# TPS5313.net
KiCad netlist of a schematic drawn in Altium Designer
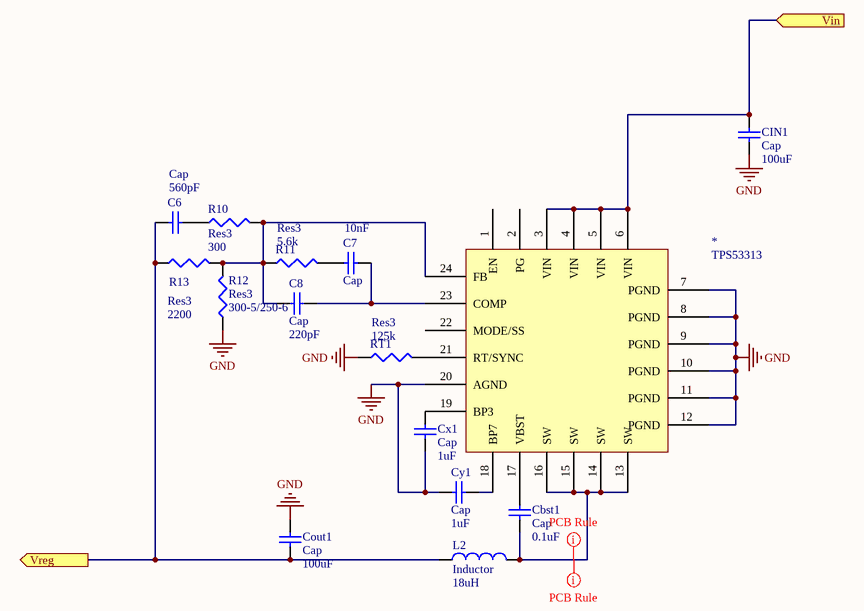
[diagram p0: TPS5313.SchDoc]

(export (version "E")
  (design (tool "Eeschema 10.0.6"))
  (components
    (comp (ref "*")
      (value "TPS53313")
      (footprint "RGE24_2P45X2P45")
      (libsource (lib "InvestiGator") (part "TPS53313"))
    )
    (comp (ref "C6")
      (value "Cap")
      (footprint "C0805")
      (description "Capacitor")
      (fields (field (name "ALTIUM_VALUE") "560pF") (field (name "PUBLISHER") "Altium Limited"))
      (libsource (lib "Miscellaneous Devices") (part "Cap"))
    )
    (comp (ref "C7")
      (value "Cap")
      (footprint "C0805")
      (description "Capacitor")
      (fields (field (name "ALTIUM_VALUE") "10nF") (field (name "PUBLISHER") "Altium Limited"))
      (libsource (lib "Miscellaneous Devices") (part "Cap"))
    )
    (comp (ref "C8")
      (value "Cap")
      (footprint "C0805")
      (description "Capacitor")
      (fields (field (name "ALTIUM_VALUE") "220pF") (field (name "PUBLISHER") "Altium Limited"))
      (libsource (lib "Miscellaneous Devices") (part "Cap"))
    )
    (comp (ref "Cbst1")
      (value "Cap")
      (footprint "C0805")
      (description "Capacitor")
      (fields (field (name "ALTIUM_VALUE") "0.1uF") (field (name "PUBLISHER") "Altium Limited"))
      (libsource (lib "Miscellaneous Devices") (part "Cap"))
    )
    (comp (ref "CIN1")
      (value "Cap")
      (footprint "C0805")
      (description "Capacitor")
      (fields (field (name "ALTIUM_VALUE") "100uF") (field (name "PUBLISHER") "Altium Limited"))
      (libsource (lib "Miscellaneous Devices") (part "Cap"))
    )
    (comp (ref "Cout1")
      (value "Cap")
      (footprint "C0805")
      (description "Capacitor")
      (fields (field (name "ALTIUM_VALUE") "100uF") (field (name "PUBLISHER") "Altium Limited"))
      (libsource (lib "Miscellaneous Devices") (part "Cap"))
    )
    (comp (ref "Cx1")
      (value "Cap")
      (footprint "C0805")
      (description "Capacitor")
      (fields (field (name "ALTIUM_VALUE") "1uF") (field (name "PUBLISHER") "Altium Limited"))
      (libsource (lib "Miscellaneous Devices") (part "Cap"))
    )
    (comp (ref "Cy1")
      (value "Cap")
      (footprint "C0805")
      (description "Capacitor")
      (fields (field (name "ALTIUM_VALUE") "1uF") (field (name "PUBLISHER") "Altium Limited"))
      (libsource (lib "Miscellaneous Devices") (part "Cap"))
    )
    (comp (ref "L2")
      (value "Inductor")
      (footprint "6-0805_L")
      (fields (field (name "ALTIUM_VALUE") "18uH") (field (name "PUBLISHER") "Altium Limited"))
      (libsource (lib "Miscellaneous Devices") (part "Inductor"))
    )
    (comp (ref "R10")
      (value "Res3")
      (footprint "6-0805_M")
      (description "Resistor")
      (fields (field (name "ALTIUM_VALUE") "300") (field (name "PUBLISHER") "Altium Limited"))
      (libsource (lib "Miscellaneous Devices") (part "Res3"))
    )
    (comp (ref "R11")
      (value "Res3")
      (footprint "6-0805_M")
      (description "Resistor")
      (fields (field (name "ALTIUM_VALUE") "5.6k") (field (name "PUBLISHER") "Altium Limited"))
      (libsource (lib "Miscellaneous Devices") (part "Res3"))
    )
    (comp (ref "R12")
      (value "Res3")
      (footprint "6-0805_M")
      (description "Resistor")
      (fields (field (name "ALTIUM_VALUE") "300-5/250-6") (field (name "PUBLISHER") "Altium Limited"))
      (libsource (lib "Miscellaneous Devices") (part "Res3"))
    )
    (comp (ref "R13")
      (value "Res3")
      (footprint "6-0805_M")
      (description "Resistor")
      (fields (field (name "ALTIUM_VALUE") "2200") (field (name "PUBLISHER") "Altium Limited"))
      (libsource (lib "Miscellaneous Devices") (part "Res3"))
    )
    (comp (ref "RT1")
      (value "Res3")
      (footprint "6-0805_M")
      (description "Resistor")
      (fields (field (name "ALTIUM_VALUE") "125k") (field (name "PUBLISHER") "Altium Limited"))
      (libsource (lib "Miscellaneous Devices") (part "Res3"))
    )
  )
  (nets
    (net (code "1") (name "/Vin") (class "Default")
      (node (ref "*") (pin "3") (pinfunction "VIN_3") (pintype "passive"))
      (node (ref "*") (pin "4") (pinfunction "VIN_4") (pintype "passive"))
      (node (ref "*") (pin "5") (pinfunction "VIN_5") (pintype "passive"))
      (node (ref "*") (pin "6") (pinfunction "VIN_6") (pintype "passive"))
      (node (ref "CIN1") (pin "1") (pinfunction "1_1") (pintype "passive"))
    )
    (net (code "2") (name "/Vreg") (class "Default")
      (node (ref "C6") (pin "1") (pinfunction "1_1") (pintype "passive"))
      (node (ref "Cout1") (pin "1") (pinfunction "1_1") (pintype "passive"))
      (node (ref "L2") (pin "1") (pinfunction "1_1") (pintype "passive"))
      (node (ref "R13") (pin "1") (pinfunction "1_1") (pintype "passive"))
    )
    (net (code "3") (name "GND") (class "Default")
      (node (ref "*") (pin "10") (pinfunction "PGND_10") (pintype "passive"))
      (node (ref "*") (pin "11") (pinfunction "PGND_11") (pintype "passive"))
      (node (ref "*") (pin "12") (pinfunction "PGND_12") (pintype "passive"))
      (node (ref "*") (pin "20") (pinfunction "AGND_20") (pintype "power_in"))
      (node (ref "*") (pin "7") (pinfunction "PGND_7") (pintype "passive"))
      (node (ref "*") (pin "8") (pinfunction "PGND_8") (pintype "passive"))
      (node (ref "*") (pin "9") (pinfunction "PGND_9") (pintype "passive"))
      (node (ref "CIN1") (pin "2") (pinfunction "2_2") (pintype "passive"))
      (node (ref "Cout1") (pin "2") (pinfunction "2_2") (pintype "passive"))
      (node (ref "Cx1") (pin "1") (pinfunction "1_1") (pintype "passive"))
      (node (ref "Cy1") (pin "2") (pinfunction "2_2") (pintype "passive"))
      (node (ref "R12") (pin "1") (pinfunction "1_1") (pintype "passive"))
      (node (ref "RT1") (pin "1") (pinfunction "1_1") (pintype "passive"))
    )
    (net (code "4") (name "Net-(*-BP3)") (class "Default")
      (node (ref "*") (pin "19") (pinfunction "BP3_19") (pintype "power_in"))
      (node (ref "Cx1") (pin "2") (pinfunction "2_2") (pintype "passive"))
    )
    (net (code "5") (name "Net-(*-BP7)") (class "Default")
      (node (ref "*") (pin "18") (pinfunction "BP7_18") (pintype "power_in"))
      (node (ref "Cy1") (pin "1") (pinfunction "1_1") (pintype "passive"))
    )
    (net (code "6") (name "Net-(*-COMP)") (class "Default")
      (node (ref "*") (pin "23") (pinfunction "COMP_23") (pintype "passive"))
      (node (ref "C7") (pin "2") (pinfunction "2_2") (pintype "passive"))
      (node (ref "C8") (pin "2") (pinfunction "2_2") (pintype "passive"))
    )
    (net (code "7") (name "Net-(*-FB)") (class "Default")
      (node (ref "*") (pin "24") (pinfunction "FB_24") (pintype "passive"))
      (node (ref "C8") (pin "1") (pinfunction "1_1") (pintype "passive"))
      (node (ref "R10") (pin "2") (pinfunction "2_2") (pintype "passive"))
      (node (ref "R11") (pin "1") (pinfunction "1_1") (pintype "passive"))
      (node (ref "R12") (pin "2") (pinfunction "2_2") (pintype "passive"))
      (node (ref "R13") (pin "2") (pinfunction "2_2") (pintype "passive"))
    )
    (net (code "8") (name "Net-(*-RT{slash}SYNC)") (class "Default")
      (node (ref "*") (pin "21") (pinfunction "RT/SYNC_21") (pintype "passive"))
      (node (ref "RT1") (pin "2") (pinfunction "2_2") (pintype "passive"))
    )
    (net (code "9") (name "Net-(*-SW-Pad13)") (class "Default")
      (node (ref "*") (pin "13") (pinfunction "SW_13") (pintype "passive"))
      (node (ref "*") (pin "14") (pinfunction "SW_14") (pintype "passive"))
      (node (ref "*") (pin "15") (pinfunction "SW_15") (pintype "passive"))
      (node (ref "*") (pin "16") (pinfunction "SW_16") (pintype "passive"))
      (node (ref "Cbst1") (pin "1") (pinfunction "1_1") (pintype "passive"))
      (node (ref "L2") (pin "2") (pinfunction "2_2") (pintype "passive"))
    )
    (net (code "10") (name "Net-(*-VBST)") (class "Default")
      (node (ref "*") (pin "17") (pinfunction "VBST_17") (pintype "power_in"))
      (node (ref "Cbst1") (pin "2") (pinfunction "2_2") (pintype "passive"))
    )
    (net (code "11") (name "Net-(C6-Pad2)") (class "Default")
      (node (ref "C6") (pin "2") (pinfunction "2_2") (pintype "passive"))
      (node (ref "R10") (pin "1") (pinfunction "1_1") (pintype "passive"))
    )
    (net (code "12") (name "Net-(C7-Pad1)") (class "Default")
      (node (ref "C7") (pin "1") (pinfunction "1_1") (pintype "passive"))
      (node (ref "R11") (pin "2") (pinfunction "2_2") (pintype "passive"))
    )
    (net (code "13") (name "unconnected-(*-EN-Pad1)") (class "Default")
      (node (ref "*") (pin "1") (pinfunction "EN_1") (pintype "passive"))
    )
    (net (code "14") (name "unconnected-(*-MODE{slash}SS-Pad22)") (class "Default")
      (node (ref "*") (pin "22") (pinfunction "MODE/SS_22") (pintype "passive"))
    )
    (net (code "15") (name "unconnected-(*-PG-Pad2)") (class "Default")
      (node (ref "*") (pin "2") (pinfunction "PG_2") (pintype "passive"))
    )
  )
)
